# usb.net
KiCad netlist of a schematic drawn in Altium Designer
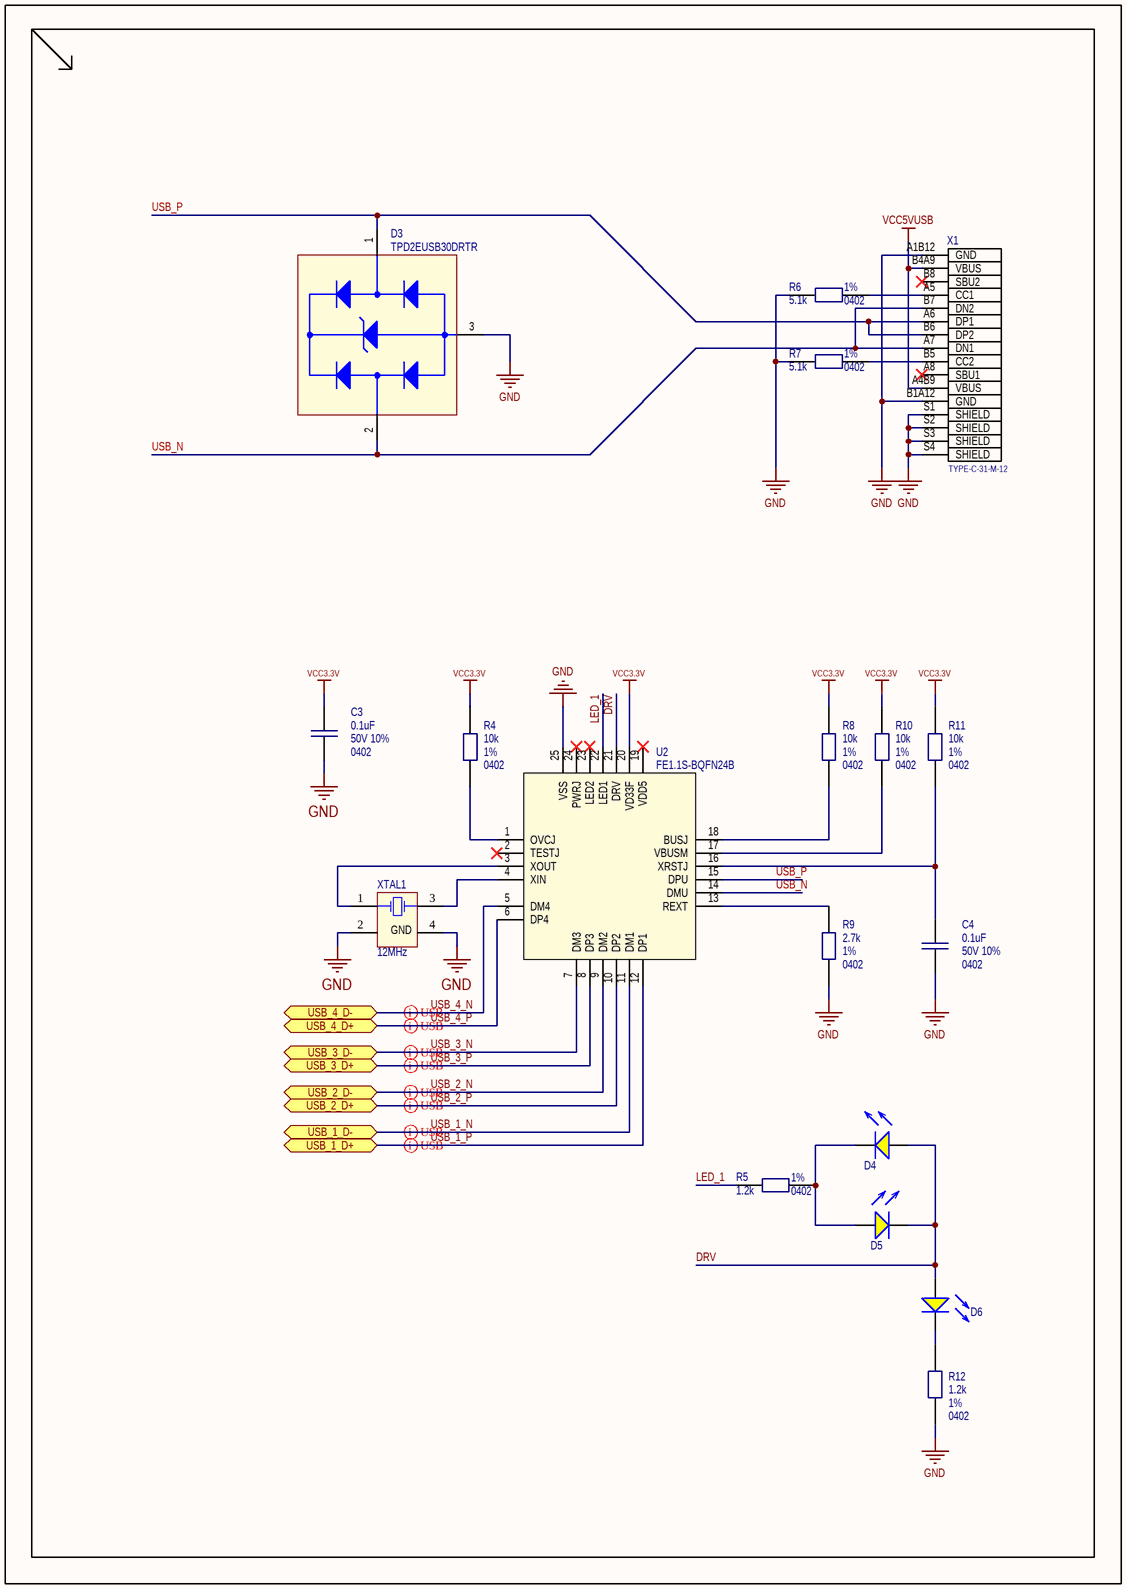
[diagram p0: usb.SchDoc]

(export (version "E")
  (design (tool "Eeschema 10.0.6"))
  (components
    (comp (ref "C3")
      (value "0.1uF")
      (footprint "C_0402")
      (description "Capacitor")
      (fields
        (field (name "PART") "CC0402KRX5R9BB104")
        (field (name "CASE/PACKAGE") "0402")
        (field (name "TOLERANCE") "50V 10%")
        (field (name "Comment") "C0402")
      )
      (libsource (lib "capacitors") (part "C0402"))
    )
    (comp (ref "C4")
      (value "0.1uF")
      (footprint "C_0402")
      (description "Capacitor")
      (fields
        (field (name "PART") "CC0402KRX5R9BB104")
        (field (name "CASE/PACKAGE") "0402")
        (field (name "TOLERANCE") "50V 10%")
        (field (name "Comment") "C0402")
      )
      (libsource (lib "capacitors") (part "C0402"))
    )
    (comp (ref "D3")
      (value "TPD2EUSB30DRTR")
      (footprint "diode:SOT-9X3-3")
      (description "2-channel ESD solution for SuperSpeed USB 3.0 interface 3-SOT-9X3 -40 to 85")
      (fields (field (name "MF") "Texas Instruments"))
      (libsource (lib "diode") (part "TPD2EUSB30DRTR"))
    )
    (comp (ref "D4")
      (value "Yellow 590nm")
      (footprint "LED 0603 YELLOW, 60°")
      (description "YELLOW LED 0603, 60°")
      (fields (field (name "PART") "APTD1608SYCK"))
      (libsource (lib "led_lcd") (part "YELLOW-LED-0603"))
    )
    (comp (ref "D5")
      (value "Yellow 590nm")
      (footprint "LED 0603 YELLOW, 60°")
      (description "YELLOW LED 0603, 60°")
      (fields (field (name "PART") "APTD1608SYCK"))
      (libsource (lib "led_lcd") (part "YELLOW-LED-0603"))
    )
    (comp (ref "D6")
      (value "Yellow 590nm")
      (footprint "LED 0603 YELLOW, 60°")
      (description "YELLOW LED 0603, 60°")
      (fields (field (name "PART") "APTD1608SYCK"))
      (libsource (lib "led_lcd") (part "YELLOW-LED-0603"))
    )
    (comp (ref "R4")
      (value "10k")
      (footprint "R_0402")
      (description "Resistor")
      (fields
        (field (name "PART") "RC0402FR-0710KL")
        (field (name "CASE/PACKAGE") "0402")
        (field (name "TOLERANCE") "1%")
        (field (name "Comment") "R0402")
      )
      (libsource (lib "resistors") (part "R0402"))
    )
    (comp (ref "R5")
      (value "1.2k")
      (footprint "R_0402")
      (description "Resistor")
      (fields
        (field (name "PART") "RC0402FR-071K2L")
        (field (name "CASE/PACKAGE") "0402")
        (field (name "TOLERANCE") "1%")
        (field (name "Comment") "R0402")
      )
      (libsource (lib "resistors") (part "R0402"))
    )
    (comp (ref "R6")
      (value "5.1k")
      (footprint "R_0402")
      (description "Resistor")
      (fields
        (field (name "PART") "RC0402FR-075K1L")
        (field (name "CASE/PACKAGE") "0402")
        (field (name "TOLERANCE") "1%")
        (field (name "Comment") "R0402")
      )
      (libsource (lib "resistors") (part "R0402"))
    )
    (comp (ref "R7")
      (value "5.1k")
      (footprint "R_0402")
      (description "Resistor")
      (fields
        (field (name "PART") "RC0402FR-075K1L")
        (field (name "CASE/PACKAGE") "0402")
        (field (name "TOLERANCE") "1%")
        (field (name "Comment") "R0402")
      )
      (libsource (lib "resistors") (part "R0402"))
    )
    (comp (ref "R8")
      (value "10k")
      (footprint "R_0402")
      (description "Resistor")
      (fields
        (field (name "PART") "RC0402FR-0710KL")
        (field (name "CASE/PACKAGE") "0402")
        (field (name "TOLERANCE") "1%")
        (field (name "Comment") "R0402")
      )
      (libsource (lib "resistors") (part "R0402"))
    )
    (comp (ref "R9")
      (value "2.7k")
      (footprint "R_0402")
      (description "Resistor")
      (fields
        (field (name "PART") "RC0402FR-072K7L")
        (field (name "CASE/PACKAGE") "0402")
        (field (name "TOLERANCE") "1%")
        (field (name "Comment") "R0402")
      )
      (libsource (lib "resistors") (part "R0402"))
    )
    (comp (ref "R10")
      (value "10k")
      (footprint "R_0402")
      (description "Resistor")
      (fields
        (field (name "PART") "RC0402FR-0710KL")
        (field (name "CASE/PACKAGE") "0402")
        (field (name "TOLERANCE") "1%")
        (field (name "Comment") "R0402")
      )
      (libsource (lib "resistors") (part "R0402"))
    )
    (comp (ref "R11")
      (value "10k")
      (footprint "R_0402")
      (description "Resistor")
      (fields
        (field (name "PART") "RC0402FR-0710KL")
        (field (name "CASE/PACKAGE") "0402")
        (field (name "TOLERANCE") "1%")
        (field (name "Comment") "R0402")
      )
      (libsource (lib "resistors") (part "R0402"))
    )
    (comp (ref "R12")
      (value "1.2k")
      (footprint "R_0402")
      (description "Resistor")
      (fields
        (field (name "PART") "RC0402FR-071K2L")
        (field (name "CASE/PACKAGE") "0402")
        (field (name "TOLERANCE") "1%")
        (field (name "Comment") "R0402")
      )
      (libsource (lib "resistors") (part "R0402"))
    )
    (comp (ref "U2")
      (value "FE1.1S-BQFN24B")
      (footprint "QFN50P400X400X80-25N-D")
      (description "USB 2.0 HIGH SPEED 4-PORT HUB CONTROLLER")
      (libsource (lib "discret_ic") (part "FE1.1S-BQFN24B"))
    )
    (comp (ref "X1")
      (value "TYPE-C-31-M-12")
      (footprint "connectors_socets:HRO_TYPE-C-31-M-12")
      (description "USB Connectors 24 Receptacle 1 8.94*7.3mm RoHS")
      (libsource (lib "connectors_socets") (part "TYPE-C-31-M-12"))
    )
    (comp (ref "XTAL1")
      (value "12MHz")
      (footprint "NX3225GA")
      (description "Crystal Oscillator")
      (fields (field (name "PART") "X322512MSB4SI"))
      (libsource (lib "crystals_oscillators") (part "SMD3225-4P"))
    )
  )
  (nets
    (net (code "1") (name "/DRV") (class "Default")
      (node (ref "D4") (pin "2") (pinfunction "2_2") (pintype "passive"))
      (node (ref "D5") (pin "1") (pinfunction "1_1") (pintype "passive"))
      (node (ref "D6") (pin "2") (pinfunction "2_2") (pintype "passive"))
      (node (ref "U2") (pin "21") (pinfunction "DRV_21") (pintype "passive"))
    )
    (net (code "2") (name "/LED_1") (class "Default")
      (node (ref "R5") (pin "2") (pinfunction "2_2") (pintype "passive"))
      (node (ref "U2") (pin "22") (pinfunction "LED1_22") (pintype "passive"))
    )
    (net (code "3") (name "/USB_1_N") (class "Default")
      (node (ref "U2") (pin "11") (pinfunction "DM1_11") (pintype "passive"))
    )
    (net (code "4") (name "/USB_1_P") (class "Default")
      (node (ref "U2") (pin "12") (pinfunction "DP1_12") (pintype "passive"))
    )
    (net (code "5") (name "/USB_2_N") (class "Default")
      (node (ref "U2") (pin "9") (pinfunction "DM2_9") (pintype "passive"))
    )
    (net (code "6") (name "/USB_2_P") (class "Default")
      (node (ref "U2") (pin "10") (pinfunction "DP2_10") (pintype "passive"))
    )
    (net (code "7") (name "/USB_3_N") (class "Default")
      (node (ref "U2") (pin "7") (pinfunction "DM3_7") (pintype "passive"))
    )
    (net (code "8") (name "/USB_3_P") (class "Default")
      (node (ref "U2") (pin "8") (pinfunction "DP3_8") (pintype "passive"))
    )
    (net (code "9") (name "/USB_4_N") (class "Default")
      (node (ref "U2") (pin "5") (pinfunction "DM4_5") (pintype "passive"))
    )
    (net (code "10") (name "/USB_4_P") (class "Default")
      (node (ref "U2") (pin "6") (pinfunction "DP4_6") (pintype "passive"))
    )
    (net (code "11") (name "/USB_N") (class "Default")
      (node (ref "D3") (pin "2") (pinfunction "GND_2") (pintype "passive"))
      (node (ref "U2") (pin "14") (pinfunction "DMU_14") (pintype "passive"))
      (node (ref "X1") (pin "A7") (pinfunction "DN1_A7") (pintype "passive"))
      (node (ref "X1") (pin "B7") (pinfunction "DN2_B7") (pintype "passive"))
    )
    (net (code "12") (name "/USB_P") (class "Default")
      (node (ref "D3") (pin "1") (pinfunction "I/O1_IN_1") (pintype "passive"))
      (node (ref "U2") (pin "15") (pinfunction "DPU_15") (pintype "passive"))
      (node (ref "X1") (pin "A6") (pinfunction "DP1_A6") (pintype "passive"))
      (node (ref "X1") (pin "B6") (pinfunction "DP2_B6") (pintype "passive"))
    )
    (net (code "13") (name "GND") (class "Default")
      (node (ref "C3") (pin "1") (pinfunction "1_1") (pintype "passive"))
      (node (ref "C4") (pin "1") (pinfunction "1_1") (pintype "passive"))
      (node (ref "D3") (pin "3") (pinfunction "I/O2_IN_3") (pintype "passive"))
      (node (ref "R12") (pin "2") (pinfunction "2_2") (pintype "passive"))
      (node (ref "R6") (pin "2") (pinfunction "2_2") (pintype "passive"))
      (node (ref "R7") (pin "2") (pinfunction "2_2") (pintype "passive"))
      (node (ref "R9") (pin "1") (pinfunction "1_1") (pintype "passive"))
      (node (ref "U2") (pin "25") (pinfunction "VSS_25") (pintype "power_in"))
      (node (ref "X1") (pin "A1B12") (pinfunction "GND_A1B12") (pintype "passive"))
      (node (ref "X1") (pin "B1A12") (pinfunction "GND_B1A12") (pintype "passive"))
      (node (ref "X1") (pin "S1") (pinfunction "SHIELD_S1") (pintype "passive"))
      (node (ref "X1") (pin "S2") (pinfunction "SHIELD_S2") (pintype "passive"))
      (node (ref "X1") (pin "S3") (pinfunction "SHIELD_S3") (pintype "passive"))
      (node (ref "X1") (pin "S4") (pinfunction "SHIELD_S4") (pintype "passive"))
      (node (ref "XTAL1") (pin "2") (pinfunction "GND_2") (pintype "passive"))
      (node (ref "XTAL1") (pin "4") (pinfunction "GND_4") (pintype "passive"))
    )
    (net (code "14") (name "Net-(D4-Pad1)") (class "Default")
      (node (ref "D4") (pin "1") (pinfunction "1_1") (pintype "passive"))
      (node (ref "D5") (pin "2") (pinfunction "2_2") (pintype "passive"))
      (node (ref "R5") (pin "1") (pinfunction "1_1") (pintype "passive"))
    )
    (net (code "15") (name "Net-(D6-Pad1)") (class "Default")
      (node (ref "D6") (pin "1") (pinfunction "1_1") (pintype "passive"))
      (node (ref "R12") (pin "1") (pinfunction "1_1") (pintype "passive"))
    )
    (net (code "16") (name "Net-(U2-BUSJ)") (class "Default")
      (node (ref "R8") (pin "1") (pinfunction "1_1") (pintype "passive"))
      (node (ref "U2") (pin "18") (pinfunction "BUSJ_18") (pintype "passive"))
    )
    (net (code "17") (name "Net-(U2-OVCJ)") (class "Default")
      (node (ref "R4") (pin "1") (pinfunction "1_1") (pintype "passive"))
      (node (ref "U2") (pin "1") (pinfunction "OVCJ_1") (pintype "passive"))
    )
    (net (code "18") (name "Net-(U2-REXT)") (class "Default")
      (node (ref "R9") (pin "2") (pinfunction "2_2") (pintype "passive"))
      (node (ref "U2") (pin "13") (pinfunction "REXT_13") (pintype "passive"))
    )
    (net (code "19") (name "Net-(U2-VBUSM)") (class "Default")
      (node (ref "R10") (pin "1") (pinfunction "1_1") (pintype "passive"))
      (node (ref "U2") (pin "17") (pinfunction "VBUSM_17") (pintype "passive"))
    )
    (net (code "20") (name "Net-(U2-XIN)") (class "Default")
      (node (ref "U2") (pin "4") (pinfunction "XIN_4") (pintype "passive"))
      (node (ref "XTAL1") (pin "3") (pinfunction "OSC2_3") (pintype "passive"))
    )
    (net (code "21") (name "Net-(U2-XOUT)") (class "Default")
      (node (ref "U2") (pin "3") (pinfunction "XOUT_3") (pintype "passive"))
      (node (ref "XTAL1") (pin "1") (pinfunction "OSC1_1") (pintype "passive"))
    )
    (net (code "22") (name "Net-(U2-XRSTJ)") (class "Default")
      (node (ref "C4") (pin "2") (pinfunction "2_2") (pintype "passive"))
      (node (ref "R11") (pin "1") (pinfunction "1_1") (pintype "passive"))
      (node (ref "U2") (pin "16") (pinfunction "XRSTJ_16") (pintype "passive"))
    )
    (net (code "23") (name "Net-(X1-CC1)") (class "Default")
      (node (ref "R6") (pin "1") (pinfunction "1_1") (pintype "passive"))
      (node (ref "X1") (pin "A5") (pinfunction "CC1_A5") (pintype "passive"))
    )
    (net (code "24") (name "Net-(X1-CC2)") (class "Default")
      (node (ref "R7") (pin "1") (pinfunction "1_1") (pintype "passive"))
      (node (ref "X1") (pin "B5") (pinfunction "CC2_B5") (pintype "passive"))
    )
    (net (code "25") (name "VCC3.3V") (class "Default")
      (node (ref "C3") (pin "2") (pinfunction "2_2") (pintype "passive"))
      (node (ref "R10") (pin "2") (pinfunction "2_2") (pintype "passive"))
      (node (ref "R11") (pin "2") (pinfunction "2_2") (pintype "passive"))
      (node (ref "R4") (pin "2") (pinfunction "2_2") (pintype "passive"))
      (node (ref "R8") (pin "2") (pinfunction "2_2") (pintype "passive"))
      (node (ref "U2") (pin "20") (pinfunction "VD33F_20") (pintype "power_in"))
    )
    (net (code "26") (name "VCC5VUSB") (class "Default")
      (node (ref "X1") (pin "A4B9") (pinfunction "VBUS_A4B9") (pintype "passive"))
      (node (ref "X1") (pin "B4A9") (pinfunction "VBUS_B4A9") (pintype "passive"))
    )
    (net (code "27") (name "unconnected-(U2-LED2-Pad23)") (class "Default")
      (node (ref "U2") (pin "23") (pinfunction "LED2_23") (pintype "passive+no_connect"))
    )
    (net (code "28") (name "unconnected-(U2-PWRJ-Pad24)") (class "Default")
      (node (ref "U2") (pin "24") (pinfunction "PWRJ_24") (pintype "passive+no_connect"))
    )
    (net (code "29") (name "unconnected-(U2-TESTJ-Pad2)") (class "Default")
      (node (ref "U2") (pin "2") (pinfunction "TESTJ_2") (pintype "passive+no_connect"))
    )
    (net (code "30") (name "unconnected-(U2-VDD5-Pad19)") (class "Default")
      (node (ref "U2") (pin "19") (pinfunction "VDD5_19") (pintype "power_in+no_connect"))
    )
    (net (code "31") (name "unconnected-(X1-SBU1-PadA8)") (class "Default")
      (node (ref "X1") (pin "A8") (pinfunction "SBU1_A8") (pintype "passive+no_connect"))
    )
    (net (code "32") (name "unconnected-(X1-SBU2-PadB8)") (class "Default")
      (node (ref "X1") (pin "B8") (pinfunction "SBU2_B8") (pintype "passive+no_connect"))
    )
  )
)
